# PM12_N5V5.net
KiCad netlist of a schematic drawn in Altium Designer
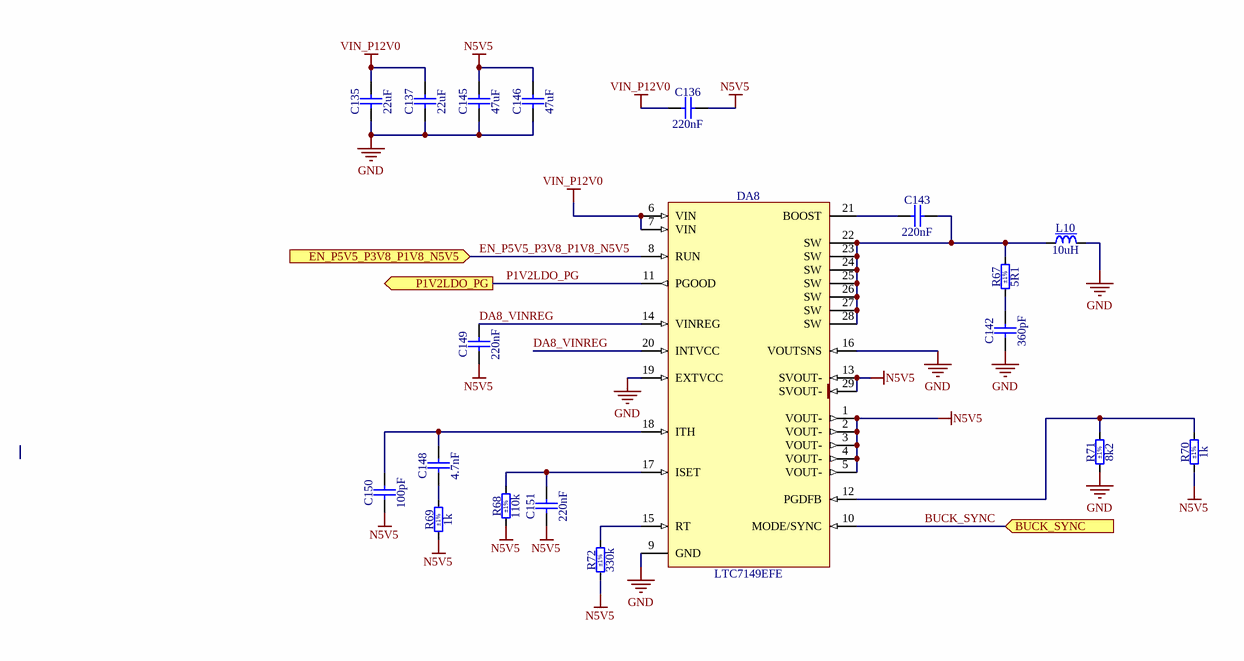
[diagram p0: PM12_N5V5.SchDoc]

(export (version "E")
  (design (tool "Eeschema 10.0.6"))
  (components
    (comp (ref "C135")
      (value "22uF")
      (footprint "CAPC3216X180N")
      (description "Non-polarised capacitor")
      (fields
        (field (name "PART NUMBER") "CC1206_22UF_25V_20%_X5R")
        (field (name "VOLTAGE") "25V")
        (field (name "AUTHOR") "CERN DEM WB")
      )
      (libsource (lib "Capacitors") (part "Capacitor - non polarized"))
    )
    (comp (ref "C136")
      (value "220nF")
      (footprint "CAPC2012X135N")
      (description "Non-polarised capacitor")
      (fields
        (field (name "PART NUMBER") "CC0805_220NF_50V_10%_X7R")
        (field (name "VOLTAGE") "50V")
        (field (name "AUTHOR") "CERN DEM JLC")
      )
      (libsource (lib "Capacitors") (part "Capacitor - non polarized"))
    )
    (comp (ref "C137")
      (value "22uF")
      (footprint "CAPC3216X180N")
      (description "Non-polarised capacitor")
      (fields
        (field (name "PART NUMBER") "CC1206_22UF_25V_20%_X5R")
        (field (name "VOLTAGE") "25V")
        (field (name "AUTHOR") "CERN DEM WB")
      )
      (libsource (lib "Capacitors") (part "Capacitor - non polarized"))
    )
    (comp (ref "C142")
      (value "360pF")
      (footprint "CAPC2013X145N")
      (description "Non-polarised capacitor")
      (fields
        (field (name "PART NUMBER") "CC0805_360PF_50V_5%_C0G")
        (field (name "VOLTAGE") "50V")
        (field (name "AUTHOR") "CERN DEM HF")
      )
      (libsource (lib "Capacitors") (part "Capacitor - non polarized"))
    )
    (comp (ref "C143")
      (value "220nF")
      (footprint "CAPC2012X135N")
      (description "Non-polarised capacitor")
      (fields
        (field (name "PART NUMBER") "CC0805_220NF_50V_10%_X7R")
        (field (name "VOLTAGE") "50V")
        (field (name "AUTHOR") "CERN DEM JLC")
      )
      (libsource (lib "Capacitors") (part "Capacitor - non polarized"))
    )
    (comp (ref "C145")
      (value "47uF")
      (footprint "CAPC3216X180N")
      (description "Non-polarised capacitor")
      (fields
        (field (name "PART NUMBER") "CC1206_47UF_25V_20%_X5R")
        (field (name "VOLTAGE") "25V")
        (field (name "AUTHOR") "CERN DEM JLC")
      )
      (libsource (lib "Capacitors") (part "Capacitor - non polarized"))
    )
    (comp (ref "C146")
      (value "47uF")
      (footprint "CAPC3216X180N")
      (description "Non-polarised capacitor")
      (fields
        (field (name "PART NUMBER") "CC1206_47UF_25V_20%_X5R")
        (field (name "VOLTAGE") "25V")
        (field (name "AUTHOR") "CERN DEM JLC")
      )
      (libsource (lib "Capacitors") (part "Capacitor - non polarized"))
    )
    (comp (ref "C148")
      (value "4.7nF")
      (footprint "CAPC2012X135N")
      (description "Non-polarised capacitor")
      (fields
        (field (name "PART NUMBER") "CC0805_4.7NF_50V_10%_X7R")
        (field (name "VOLTAGE") "50V")
        (field (name "AUTHOR") "CERN DEM JLC")
      )
      (libsource (lib "Capacitors") (part "Capacitor - non polarized"))
    )
    (comp (ref "C149")
      (value "220nF")
      (footprint "CAPC2012X135N")
      (description "Non-polarised capacitor")
      (fields
        (field (name "PART NUMBER") "CC0805_220NF_50V_10%_X7R")
        (field (name "VOLTAGE") "50V")
        (field (name "AUTHOR") "CERN DEM JLC")
      )
      (libsource (lib "Capacitors") (part "Capacitor - non polarized"))
    )
    (comp (ref "C150")
      (value "100pF")
      (footprint "CAPC2012X135N")
      (description "Non-polarised capacitor")
      (fields
        (field (name "PART NUMBER") "CC0805_100PF_50V_5%_NP0")
        (field (name "VOLTAGE") "50V")
        (field (name "AUTHOR") "CERN DEM JLC")
      )
      (libsource (lib "Capacitors") (part "Capacitor - non polarized"))
    )
    (comp (ref "C151")
      (value "220nF")
      (footprint "CAPC2012X135N")
      (description "Non-polarised capacitor")
      (fields
        (field (name "PART NUMBER") "CC0805_220NF_50V_10%_X7R")
        (field (name "VOLTAGE") "50V")
        (field (name "AUTHOR") "CERN DEM JLC")
      )
      (libsource (lib "Capacitors") (part "Capacitor - non polarized"))
    )
    (comp (ref "DA8")
      (value "LTC7149EFE")
      (footprint "SOP65P640X120-29N-R274X475")
      (description "60V, 4A Synchronous  Step-Down Regulator for Inverting Outputs")
      (fields (field (name "MANUFACTURER") "LINEAR TECHNOLOGY") (field (name "AUTHOR") "CERN DEM HF"))
      (libsource (lib "ICs And Semiconductors") (part "LTC7149XFE"))
    )
    (comp (ref "L10")
      (value "10uH")
      (footprint "IND_VISHAY_IHPL4040DZ-01")
      (description "Inductor With Core")
      (fields
        (field (name "PART NUMBER") "IND4040_10UH_20%_VISHAY_IHLP-4040DZ-01")
        (field (name "POWER") "6.8A")
        (field (name "AUTHOR") "CERN DEM HF")
      )
      (libsource (lib "Inductors & Transformers") (part "Inductor With Magnetic core"))
    )
    (comp (ref "R67")
      (value "5R1")
      (footprint "RESC2012X60N")
      (description "Resistor - 1%")
      (fields
        (field (name "TOLERANCE") "±1%")
        (field (name "PART NUMBER") "R0805_5R1_1%_0.125W_100PPM")
        (field (name "POWER") "0.125W")
        (field (name "AUTHOR") "CERN DEM HF")
      )
      (libsource (lib "Resistors") (part "Resistor - 1%"))
    )
    (comp (ref "R68")
      (value "110k")
      (footprint "RESC2012X60N")
      (description "Resistor - 1%")
      (fields
        (field (name "TOLERANCE") "±1%")
        (field (name "PART NUMBER") "R0805_110K_1%_0.125W_100PPM")
        (field (name "POWER") "0.125W")
        (field (name "AUTHOR") "CERN DEM JLC")
      )
      (libsource (lib "Resistors") (part "Resistor - 1%"))
    )
    (comp (ref "R69")
      (value "1k")
      (footprint "RESC2012X60N")
      (description "Resistor - 1%")
      (fields
        (field (name "TOLERANCE") "±1%")
        (field (name "PART NUMBER") "R0805_1K_1%_0.125W_100PPM")
        (field (name "POWER") "0.125W")
        (field (name "AUTHOR") "CERN DEM JLC")
      )
      (libsource (lib "Resistors") (part "Resistor - 1%"))
    )
    (comp (ref "R70")
      (value "1k")
      (footprint "RESC2012X60N")
      (description "Resistor - 1%")
      (fields
        (field (name "TOLERANCE") "±1%")
        (field (name "PART NUMBER") "R0805_1K_1%_0.125W_100PPM")
        (field (name "POWER") "0.125W")
        (field (name "AUTHOR") "CERN DEM JLC")
      )
      (libsource (lib "Resistors") (part "Resistor - 1%"))
    )
    (comp (ref "R71")
      (value "8k2")
      (footprint "RESC2012X60N")
      (description "Resistor - 1%")
      (fields
        (field (name "TOLERANCE") "±1%")
        (field (name "PART NUMBER") "R0805_8K2_1%_0.125W_100PPM")
        (field (name "POWER") "0.125W")
        (field (name "AUTHOR") "CERN DEM JLC")
      )
      (libsource (lib "Resistors") (part "Resistor - 1%"))
    )
    (comp (ref "R72")
      (value "330k")
      (footprint "RESC2012X60N")
      (description "Resistor - 1%")
      (fields
        (field (name "TOLERANCE") "±1%")
        (field (name "PART NUMBER") "R0805_330K_1%_0.125W_100PPM")
        (field (name "POWER") "0.125W")
        (field (name "AUTHOR") "CERN DEM JLC")
      )
      (libsource (lib "Resistors") (part "Resistor - 1%"))
    )
  )
  (nets
    (net (code "1") (name "/BUCK_SYNC") (class "Default")
      (node (ref "DA8") (pin "10") (pinfunction "MODE/SYNC_10") (pintype "input"))
    )
    (net (code "2") (name "/DA8_VINREG") (class "Default")
      (node (ref "C149") (pin "2") (pinfunction "2_2") (pintype "passive"))
      (node (ref "DA8") (pin "14") (pinfunction "VINREG_14") (pintype "input"))
      (node (ref "DA8") (pin "20") (pinfunction "INTVCC_20") (pintype "input"))
    )
    (net (code "3") (name "/EN_P5V5_P3V8_P1V8_N5V5") (class "Default")
      (node (ref "DA8") (pin "8") (pinfunction "RUN_8") (pintype "input"))
    )
    (net (code "4") (name "/P1V2LDO_PG") (class "Default")
      (node (ref "DA8") (pin "11") (pinfunction "PGOOD_11") (pintype "output"))
    )
    (net (code "5") (name "GND") (class "Default")
      (node (ref "C135") (pin "1") (pinfunction "1_1") (pintype "passive"))
      (node (ref "C137") (pin "1") (pinfunction "1_1") (pintype "passive"))
      (node (ref "C142") (pin "1") (pinfunction "1_1") (pintype "passive"))
      (node (ref "C145") (pin "1") (pinfunction "1_1") (pintype "passive"))
      (node (ref "C146") (pin "1") (pinfunction "1_1") (pintype "passive"))
      (node (ref "DA8") (pin "16") (pinfunction "VOUTSNS_16") (pintype "input"))
      (node (ref "DA8") (pin "19") (pinfunction "EXTVCC_19") (pintype "input"))
      (node (ref "DA8") (pin "9") (pinfunction "GND_9") (pintype "power_in"))
      (node (ref "L10") (pin "2") (pinfunction "2_2") (pintype "passive"))
      (node (ref "R71") (pin "1") (pinfunction "1_1") (pintype "passive"))
    )
    (net (code "6") (name "N5V5") (class "Default")
      (node (ref "C136") (pin "2") (pinfunction "2_2") (pintype "passive"))
      (node (ref "C145") (pin "2") (pinfunction "2_2") (pintype "passive"))
      (node (ref "C146") (pin "2") (pinfunction "2_2") (pintype "passive"))
      (node (ref "C149") (pin "1") (pinfunction "1_1") (pintype "passive"))
      (node (ref "C150") (pin "1") (pinfunction "1_1") (pintype "passive"))
      (node (ref "C151") (pin "1") (pinfunction "1_1") (pintype "passive"))
      (node (ref "DA8") (pin "1") (pinfunction "VOUT-_1") (pintype "output"))
      (node (ref "DA8") (pin "13") (pinfunction "SVOUT-_13") (pintype "input"))
      (node (ref "DA8") (pin "2") (pinfunction "VOUT-_2") (pintype "output"))
      (node (ref "DA8") (pin "29") (pinfunction "SVOUT-_29") (pintype "input"))
      (node (ref "DA8") (pin "3") (pinfunction "VOUT-_3") (pintype "output"))
      (node (ref "DA8") (pin "4") (pinfunction "VOUT-_4") (pintype "output"))
      (node (ref "DA8") (pin "5") (pinfunction "VOUT-_5") (pintype "output"))
      (node (ref "R68") (pin "1") (pinfunction "1_1") (pintype "passive"))
      (node (ref "R69") (pin "1") (pinfunction "1_1") (pintype "passive"))
      (node (ref "R70") (pin "1") (pinfunction "1_1") (pintype "passive"))
      (node (ref "R72") (pin "1") (pinfunction "1_1") (pintype "passive"))
    )
    (net (code "7") (name "Net-(C142-Pad2)") (class "Default")
      (node (ref "C142") (pin "2") (pinfunction "2_2") (pintype "passive"))
      (node (ref "R67") (pin "1") (pinfunction "1_1") (pintype "passive"))
    )
    (net (code "8") (name "Net-(C143-Pad2)") (class "Default")
      (node (ref "C143") (pin "2") (pinfunction "2_2") (pintype "passive"))
      (node (ref "DA8") (pin "22") (pinfunction "SW_22") (pintype "power_in"))
      (node (ref "DA8") (pin "23") (pinfunction "SW_23") (pintype "power_in"))
      (node (ref "DA8") (pin "24") (pinfunction "SW_24") (pintype "power_in"))
      (node (ref "DA8") (pin "25") (pinfunction "SW_25") (pintype "power_in"))
      (node (ref "DA8") (pin "26") (pinfunction "SW_26") (pintype "power_in"))
      (node (ref "DA8") (pin "27") (pinfunction "SW_27") (pintype "power_in"))
      (node (ref "DA8") (pin "28") (pinfunction "SW_28") (pintype "power_in"))
      (node (ref "L10") (pin "1") (pinfunction "1_1") (pintype "passive"))
      (node (ref "R67") (pin "2") (pinfunction "2_2") (pintype "passive"))
    )
    (net (code "9") (name "Net-(C148-Pad1)") (class "Default")
      (node (ref "C148") (pin "1") (pinfunction "1_1") (pintype "passive"))
      (node (ref "R69") (pin "2") (pinfunction "2_2") (pintype "passive"))
    )
    (net (code "10") (name "Net-(DA8-BOOST)") (class "Default")
      (node (ref "C143") (pin "1") (pinfunction "1_1") (pintype "passive"))
      (node (ref "DA8") (pin "21") (pinfunction "BOOST_21") (pintype "passive"))
    )
    (net (code "11") (name "Net-(DA8-ISET)") (class "Default")
      (node (ref "C151") (pin "2") (pinfunction "2_2") (pintype "passive"))
      (node (ref "DA8") (pin "17") (pinfunction "ISET_17") (pintype "input"))
      (node (ref "R68") (pin "2") (pinfunction "2_2") (pintype "passive"))
    )
    (net (code "12") (name "Net-(DA8-ITH)") (class "Default")
      (node (ref "C148") (pin "2") (pinfunction "2_2") (pintype "passive"))
      (node (ref "C150") (pin "2") (pinfunction "2_2") (pintype "passive"))
      (node (ref "DA8") (pin "18") (pinfunction "ITH_18") (pintype "input"))
    )
    (net (code "13") (name "Net-(DA8-PGDFB)") (class "Default")
      (node (ref "DA8") (pin "12") (pinfunction "PGDFB_12") (pintype "input"))
      (node (ref "R70") (pin "2") (pinfunction "2_2") (pintype "passive"))
      (node (ref "R71") (pin "2") (pinfunction "2_2") (pintype "passive"))
    )
    (net (code "14") (name "Net-(DA8-RT)") (class "Default")
      (node (ref "DA8") (pin "15") (pinfunction "RT_15") (pintype "input"))
      (node (ref "R72") (pin "2") (pinfunction "2_2") (pintype "passive"))
    )
    (net (code "15") (name "VIN_P12V0") (class "Default")
      (node (ref "C135") (pin "2") (pinfunction "2_2") (pintype "passive"))
      (node (ref "C136") (pin "1") (pinfunction "1_1") (pintype "passive"))
      (node (ref "C137") (pin "2") (pinfunction "2_2") (pintype "passive"))
      (node (ref "DA8") (pin "6") (pinfunction "VIN_6") (pintype "input"))
      (node (ref "DA8") (pin "7") (pinfunction "VIN_7") (pintype "input"))
    )
  )
)
